# Chov2_led.net
KiCad netlist of a schematic drawn in Altium Designer
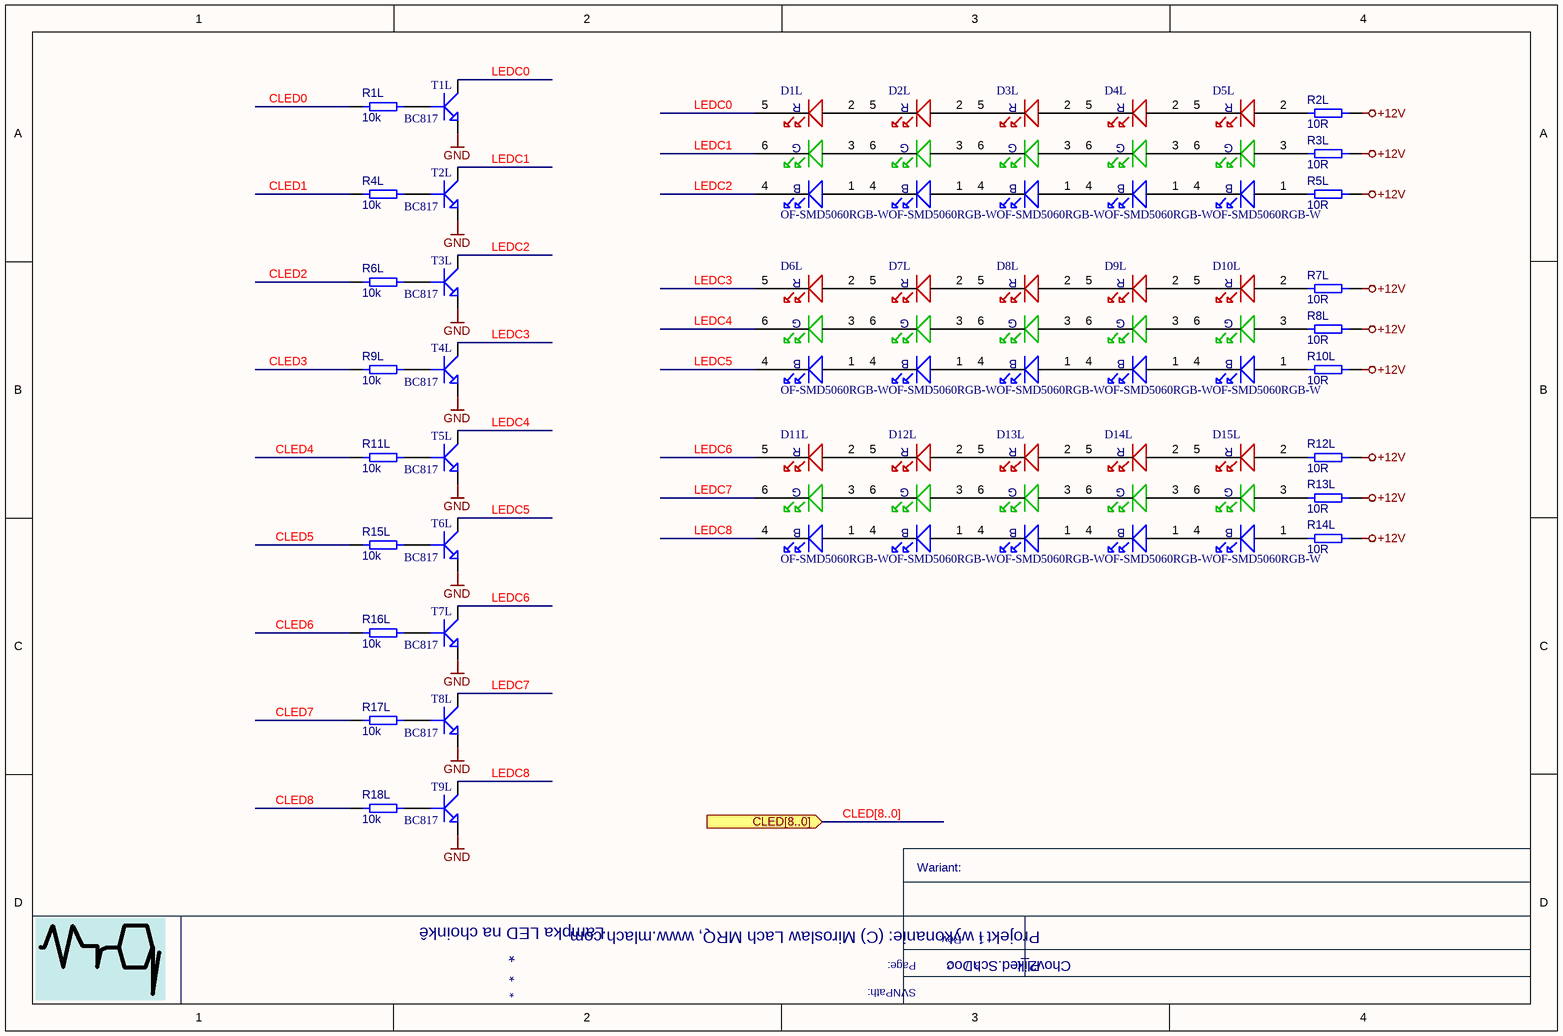
[diagram p0: Chov2_led.SchDoc]

(export (version "E")
  (design (tool "Eeschema 10.0.6"))
  (components
    (comp (ref "D1L")
      (value "OF-SMD5060RGB-W")
      (footprint "OF-SMD5060RGB-W")
      (libsource (lib "Parts") (part "OF-SMD5060RGB-W"))
    )
    (comp (ref "D2L")
      (value "OF-SMD5060RGB-W")
      (footprint "OF-SMD5060RGB-W")
      (libsource (lib "Parts") (part "OF-SMD5060RGB-W"))
    )
    (comp (ref "D3L")
      (value "OF-SMD5060RGB-W")
      (footprint "OF-SMD5060RGB-W")
      (libsource (lib "Parts") (part "OF-SMD5060RGB-W"))
    )
    (comp (ref "D4L")
      (value "OF-SMD5060RGB-W")
      (footprint "OF-SMD5060RGB-W")
      (libsource (lib "Parts") (part "OF-SMD5060RGB-W"))
    )
    (comp (ref "D5L")
      (value "OF-SMD5060RGB-W")
      (footprint "OF-SMD5060RGB-W")
      (libsource (lib "Parts") (part "OF-SMD5060RGB-W"))
    )
    (comp (ref "D6L")
      (value "OF-SMD5060RGB-W")
      (footprint "OF-SMD5060RGB-W")
      (libsource (lib "Parts") (part "OF-SMD5060RGB-W"))
    )
    (comp (ref "D7L")
      (value "OF-SMD5060RGB-W")
      (footprint "OF-SMD5060RGB-W")
      (libsource (lib "Parts") (part "OF-SMD5060RGB-W"))
    )
    (comp (ref "D8L")
      (value "OF-SMD5060RGB-W")
      (footprint "OF-SMD5060RGB-W")
      (libsource (lib "Parts") (part "OF-SMD5060RGB-W"))
    )
    (comp (ref "D9L")
      (value "OF-SMD5060RGB-W")
      (footprint "OF-SMD5060RGB-W")
      (libsource (lib "Parts") (part "OF-SMD5060RGB-W"))
    )
    (comp (ref "D10L")
      (value "OF-SMD5060RGB-W")
      (footprint "OF-SMD5060RGB-W")
      (libsource (lib "Parts") (part "OF-SMD5060RGB-W"))
    )
    (comp (ref "D11L")
      (value "OF-SMD5060RGB-W")
      (footprint "OF-SMD5060RGB-W")
      (libsource (lib "Parts") (part "OF-SMD5060RGB-W"))
    )
    (comp (ref "D12L")
      (value "OF-SMD5060RGB-W")
      (footprint "OF-SMD5060RGB-W")
      (libsource (lib "Parts") (part "OF-SMD5060RGB-W"))
    )
    (comp (ref "D13L")
      (value "OF-SMD5060RGB-W")
      (footprint "OF-SMD5060RGB-W")
      (libsource (lib "Parts") (part "OF-SMD5060RGB-W"))
    )
    (comp (ref "D14L")
      (value "OF-SMD5060RGB-W")
      (footprint "OF-SMD5060RGB-W")
      (libsource (lib "Parts") (part "OF-SMD5060RGB-W"))
    )
    (comp (ref "D15L")
      (value "OF-SMD5060RGB-W")
      (footprint "OF-SMD5060RGB-W")
      (libsource (lib "Parts") (part "OF-SMD5060RGB-W"))
    )
    (comp (ref "R1L")
      (value "0603WGF10KT5E")
      (footprint "0603-IPC")
      (fields (field (name "OTHERPARAMS") "10k") (field (name "TOLERANCE") "1%"))
      (libsource (lib "Parts") (part "R"))
    )
    (comp (ref "R2L")
      (value "0805S8F100JT5E")
      (footprint "0805")
      (fields (field (name "OTHERPARAMS") "10R") (field (name "TOLERANCE") "1%"))
      (libsource (lib "Parts") (part "R"))
    )
    (comp (ref "R3L")
      (value "0805S8F100JT5E")
      (footprint "0805")
      (fields (field (name "OTHERPARAMS") "10R") (field (name "TOLERANCE") "1%"))
      (libsource (lib "Parts") (part "R"))
    )
    (comp (ref "R4L")
      (value "0603WGF10KT5E")
      (footprint "0603-IPC")
      (fields (field (name "OTHERPARAMS") "10k") (field (name "TOLERANCE") "1%"))
      (libsource (lib "Parts") (part "R"))
    )
    (comp (ref "R5L")
      (value "0805S8F100JT5E")
      (footprint "0805")
      (fields (field (name "OTHERPARAMS") "10R") (field (name "TOLERANCE") "1%"))
      (libsource (lib "Parts") (part "R"))
    )
    (comp (ref "R6L")
      (value "0603WGF10KT5E")
      (footprint "0603-IPC")
      (fields (field (name "OTHERPARAMS") "10k") (field (name "TOLERANCE") "1%"))
      (libsource (lib "Parts") (part "R"))
    )
    (comp (ref "R7L")
      (value "0805S8F100JT5E")
      (footprint "0805")
      (fields (field (name "OTHERPARAMS") "10R") (field (name "TOLERANCE") "1%"))
      (libsource (lib "Parts") (part "R"))
    )
    (comp (ref "R8L")
      (value "0805S8F100JT5E")
      (footprint "0805")
      (fields (field (name "OTHERPARAMS") "10R") (field (name "TOLERANCE") "1%"))
      (libsource (lib "Parts") (part "R"))
    )
    (comp (ref "R9L")
      (value "0603WGF10KT5E")
      (footprint "0603-IPC")
      (fields (field (name "OTHERPARAMS") "10k") (field (name "TOLERANCE") "1%"))
      (libsource (lib "Parts") (part "R"))
    )
    (comp (ref "R10L")
      (value "0805S8F100JT5E")
      (footprint "0805")
      (fields (field (name "OTHERPARAMS") "10R") (field (name "TOLERANCE") "1%"))
      (libsource (lib "Parts") (part "R"))
    )
    (comp (ref "R11L")
      (value "0603WGF10KT5E")
      (footprint "0603-IPC")
      (fields (field (name "OTHERPARAMS") "10k") (field (name "TOLERANCE") "1%"))
      (libsource (lib "Parts") (part "R"))
    )
    (comp (ref "R12L")
      (value "0805S8F100JT5E")
      (footprint "0805")
      (fields (field (name "OTHERPARAMS") "10R") (field (name "TOLERANCE") "1%"))
      (libsource (lib "Parts") (part "R"))
    )
    (comp (ref "R13L")
      (value "0805S8F100JT5E")
      (footprint "0805")
      (fields (field (name "OTHERPARAMS") "10R") (field (name "TOLERANCE") "1%"))
      (libsource (lib "Parts") (part "R"))
    )
    (comp (ref "R14L")
      (value "0805S8F100JT5E")
      (footprint "0805")
      (fields (field (name "OTHERPARAMS") "10R") (field (name "TOLERANCE") "1%"))
      (libsource (lib "Parts") (part "R"))
    )
    (comp (ref "R15L")
      (value "0603WGF10KT5E")
      (footprint "0603-IPC")
      (fields (field (name "OTHERPARAMS") "10k") (field (name "TOLERANCE") "1%"))
      (libsource (lib "Parts") (part "R"))
    )
    (comp (ref "R16L")
      (value "0603WGF10KT5E")
      (footprint "0603-IPC")
      (fields (field (name "OTHERPARAMS") "10k") (field (name "TOLERANCE") "1%"))
      (libsource (lib "Parts") (part "R"))
    )
    (comp (ref "R17L")
      (value "0603WGF10KT5E")
      (footprint "0603-IPC")
      (fields (field (name "OTHERPARAMS") "10k") (field (name "TOLERANCE") "1%"))
      (libsource (lib "Parts") (part "R"))
    )
    (comp (ref "R18L")
      (value "0603WGF10KT5E")
      (footprint "0603-IPC")
      (fields (field (name "OTHERPARAMS") "10k") (field (name "TOLERANCE") "1%"))
      (libsource (lib "Parts") (part "R"))
    )
    (comp (ref "T1L") (value "BC817") (footprint "SOT23-3") (libsource (lib "Parts") (part "NPN_SOT23-3")))
    (comp (ref "T2L") (value "BC817") (footprint "SOT23-3") (libsource (lib "Parts") (part "NPN_SOT23-3")))
    (comp (ref "T3L") (value "BC817") (footprint "SOT23-3") (libsource (lib "Parts") (part "NPN_SOT23-3")))
    (comp (ref "T4L") (value "BC817") (footprint "SOT23-3") (libsource (lib "Parts") (part "NPN_SOT23-3")))
    (comp (ref "T5L") (value "BC817") (footprint "SOT23-3") (libsource (lib "Parts") (part "NPN_SOT23-3")))
    (comp (ref "T6L") (value "BC817") (footprint "SOT23-3") (libsource (lib "Parts") (part "NPN_SOT23-3")))
    (comp (ref "T7L") (value "BC817") (footprint "SOT23-3") (libsource (lib "Parts") (part "NPN_SOT23-3")))
    (comp (ref "T8L") (value "BC817") (footprint "SOT23-3") (libsource (lib "Parts") (part "NPN_SOT23-3")))
    (comp (ref "T9L") (value "BC817") (footprint "SOT23-3") (libsource (lib "Parts") (part "NPN_SOT23-3")))
  )
  (nets
    (net (code "1") (name "+12V") (class "Default")
      (node (ref "R10L") (pin "2") (pinfunction "2_2") (pintype "passive"))
      (node (ref "R12L") (pin "2") (pinfunction "2_2") (pintype "passive"))
      (node (ref "R13L") (pin "2") (pinfunction "2_2") (pintype "passive"))
      (node (ref "R14L") (pin "2") (pinfunction "2_2") (pintype "passive"))
      (node (ref "R2L") (pin "2") (pinfunction "2_2") (pintype "passive"))
      (node (ref "R3L") (pin "2") (pinfunction "2_2") (pintype "passive"))
      (node (ref "R5L") (pin "2") (pinfunction "2_2") (pintype "passive"))
      (node (ref "R7L") (pin "2") (pinfunction "2_2") (pintype "passive"))
      (node (ref "R8L") (pin "2") (pinfunction "2_2") (pintype "passive"))
    )
    (net (code "2") (name "/CLED0") (class "Default")
      (node (ref "R1L") (pin "1") (pinfunction "1_1") (pintype "passive"))
    )
    (net (code "3") (name "/CLED1") (class "Default")
      (node (ref "R4L") (pin "1") (pinfunction "1_1") (pintype "passive"))
    )
    (net (code "4") (name "/CLED2") (class "Default")
      (node (ref "R6L") (pin "1") (pinfunction "1_1") (pintype "passive"))
    )
    (net (code "5") (name "/CLED3") (class "Default")
      (node (ref "R9L") (pin "1") (pinfunction "1_1") (pintype "passive"))
    )
    (net (code "6") (name "/CLED4") (class "Default")
      (node (ref "R11L") (pin "1") (pinfunction "1_1") (pintype "passive"))
    )
    (net (code "7") (name "/CLED5") (class "Default")
      (node (ref "R15L") (pin "1") (pinfunction "1_1") (pintype "passive"))
    )
    (net (code "8") (name "/CLED6") (class "Default")
      (node (ref "R16L") (pin "1") (pinfunction "1_1") (pintype "passive"))
    )
    (net (code "9") (name "/CLED7") (class "Default")
      (node (ref "R17L") (pin "1") (pinfunction "1_1") (pintype "passive"))
    )
    (net (code "10") (name "/CLED8") (class "Default")
      (node (ref "R18L") (pin "1") (pinfunction "1_1") (pintype "passive"))
    )
    (net (code "12") (name "/LEDC0") (class "Default")
      (node (ref "D1L") (pin "5") (pinfunction "CATH_5") (pintype "passive"))
      (node (ref "T1L") (pin "3") (pinfunction "3_3") (pintype "passive"))
    )
    (net (code "13") (name "/LEDC1") (class "Default")
      (node (ref "D1L") (pin "6") (pinfunction "CATH_6") (pintype "passive"))
      (node (ref "T2L") (pin "3") (pinfunction "3_3") (pintype "passive"))
    )
    (net (code "14") (name "/LEDC2") (class "Default")
      (node (ref "D1L") (pin "4") (pinfunction "CATH_4") (pintype "passive"))
      (node (ref "T3L") (pin "3") (pinfunction "3_3") (pintype "passive"))
    )
    (net (code "15") (name "/LEDC3") (class "Default")
      (node (ref "D6L") (pin "5") (pinfunction "CATH_5") (pintype "passive"))
      (node (ref "T4L") (pin "3") (pinfunction "3_3") (pintype "passive"))
    )
    (net (code "16") (name "/LEDC4") (class "Default")
      (node (ref "D6L") (pin "6") (pinfunction "CATH_6") (pintype "passive"))
      (node (ref "T5L") (pin "3") (pinfunction "3_3") (pintype "passive"))
    )
    (net (code "17") (name "/LEDC5") (class "Default")
      (node (ref "D6L") (pin "4") (pinfunction "CATH_4") (pintype "passive"))
      (node (ref "T6L") (pin "3") (pinfunction "3_3") (pintype "passive"))
    )
    (net (code "18") (name "/LEDC6") (class "Default")
      (node (ref "D11L") (pin "5") (pinfunction "CATH_5") (pintype "passive"))
      (node (ref "T7L") (pin "3") (pinfunction "3_3") (pintype "passive"))
    )
    (net (code "19") (name "/LEDC7") (class "Default")
      (node (ref "D11L") (pin "6") (pinfunction "CATH_6") (pintype "passive"))
      (node (ref "T8L") (pin "3") (pinfunction "3_3") (pintype "passive"))
    )
    (net (code "20") (name "/LEDC8") (class "Default")
      (node (ref "D11L") (pin "4") (pinfunction "CATH_4") (pintype "passive"))
      (node (ref "T9L") (pin "3") (pinfunction "3_3") (pintype "passive"))
    )
    (net (code "21") (name "GND") (class "Default")
      (node (ref "T1L") (pin "2") (pinfunction "2_2") (pintype "passive"))
      (node (ref "T2L") (pin "2") (pinfunction "2_2") (pintype "passive"))
      (node (ref "T3L") (pin "2") (pinfunction "2_2") (pintype "passive"))
      (node (ref "T4L") (pin "2") (pinfunction "2_2") (pintype "passive"))
      (node (ref "T5L") (pin "2") (pinfunction "2_2") (pintype "passive"))
      (node (ref "T6L") (pin "2") (pinfunction "2_2") (pintype "passive"))
      (node (ref "T7L") (pin "2") (pinfunction "2_2") (pintype "passive"))
      (node (ref "T8L") (pin "2") (pinfunction "2_2") (pintype "passive"))
      (node (ref "T9L") (pin "2") (pinfunction "2_2") (pintype "passive"))
    )
    (net (code "22") (name "Net-(D1L-ANOD-Pad1)") (class "Default")
      (node (ref "D1L") (pin "1") (pinfunction "ANOD_1") (pintype "passive"))
      (node (ref "D2L") (pin "4") (pinfunction "CATH_4") (pintype "passive"))
    )
    (net (code "23") (name "Net-(D1L-ANOD-Pad2)") (class "Default")
      (node (ref "D1L") (pin "2") (pinfunction "ANOD_2") (pintype "passive"))
      (node (ref "D2L") (pin "5") (pinfunction "CATH_5") (pintype "passive"))
    )
    (net (code "24") (name "Net-(D1L-ANOD-Pad3)") (class "Default")
      (node (ref "D1L") (pin "3") (pinfunction "ANOD_3") (pintype "passive"))
      (node (ref "D2L") (pin "6") (pinfunction "CATH_6") (pintype "passive"))
    )
    (net (code "25") (name "Net-(D2L-ANOD-Pad1)") (class "Default")
      (node (ref "D2L") (pin "1") (pinfunction "ANOD_1") (pintype "passive"))
      (node (ref "D3L") (pin "4") (pinfunction "CATH_4") (pintype "passive"))
    )
    (net (code "26") (name "Net-(D2L-ANOD-Pad2)") (class "Default")
      (node (ref "D2L") (pin "2") (pinfunction "ANOD_2") (pintype "passive"))
      (node (ref "D3L") (pin "5") (pinfunction "CATH_5") (pintype "passive"))
    )
    (net (code "27") (name "Net-(D2L-ANOD-Pad3)") (class "Default")
      (node (ref "D2L") (pin "3") (pinfunction "ANOD_3") (pintype "passive"))
      (node (ref "D3L") (pin "6") (pinfunction "CATH_6") (pintype "passive"))
    )
    (net (code "28") (name "Net-(D3L-ANOD-Pad1)") (class "Default")
      (node (ref "D3L") (pin "1") (pinfunction "ANOD_1") (pintype "passive"))
      (node (ref "D4L") (pin "4") (pinfunction "CATH_4") (pintype "passive"))
    )
    (net (code "29") (name "Net-(D3L-ANOD-Pad2)") (class "Default")
      (node (ref "D3L") (pin "2") (pinfunction "ANOD_2") (pintype "passive"))
      (node (ref "D4L") (pin "5") (pinfunction "CATH_5") (pintype "passive"))
    )
    (net (code "30") (name "Net-(D3L-ANOD-Pad3)") (class "Default")
      (node (ref "D3L") (pin "3") (pinfunction "ANOD_3") (pintype "passive"))
      (node (ref "D4L") (pin "6") (pinfunction "CATH_6") (pintype "passive"))
    )
    (net (code "31") (name "Net-(D4L-ANOD-Pad1)") (class "Default")
      (node (ref "D4L") (pin "1") (pinfunction "ANOD_1") (pintype "passive"))
      (node (ref "D5L") (pin "4") (pinfunction "CATH_4") (pintype "passive"))
    )
    (net (code "32") (name "Net-(D4L-ANOD-Pad2)") (class "Default")
      (node (ref "D4L") (pin "2") (pinfunction "ANOD_2") (pintype "passive"))
      (node (ref "D5L") (pin "5") (pinfunction "CATH_5") (pintype "passive"))
    )
    (net (code "33") (name "Net-(D4L-ANOD-Pad3)") (class "Default")
      (node (ref "D4L") (pin "3") (pinfunction "ANOD_3") (pintype "passive"))
      (node (ref "D5L") (pin "6") (pinfunction "CATH_6") (pintype "passive"))
    )
    (net (code "34") (name "Net-(D5L-ANOD-Pad1)") (class "Default")
      (node (ref "D5L") (pin "1") (pinfunction "ANOD_1") (pintype "passive"))
      (node (ref "R5L") (pin "1") (pinfunction "1_1") (pintype "passive"))
    )
    (net (code "35") (name "Net-(D5L-ANOD-Pad2)") (class "Default")
      (node (ref "D5L") (pin "2") (pinfunction "ANOD_2") (pintype "passive"))
      (node (ref "R2L") (pin "1") (pinfunction "1_1") (pintype "passive"))
    )
    (net (code "36") (name "Net-(D5L-ANOD-Pad3)") (class "Default")
      (node (ref "D5L") (pin "3") (pinfunction "ANOD_3") (pintype "passive"))
      (node (ref "R3L") (pin "1") (pinfunction "1_1") (pintype "passive"))
    )
    (net (code "37") (name "Net-(D6L-ANOD-Pad1)") (class "Default")
      (node (ref "D6L") (pin "1") (pinfunction "ANOD_1") (pintype "passive"))
      (node (ref "D7L") (pin "4") (pinfunction "CATH_4") (pintype "passive"))
    )
    (net (code "38") (name "Net-(D6L-ANOD-Pad2)") (class "Default")
      (node (ref "D6L") (pin "2") (pinfunction "ANOD_2") (pintype "passive"))
      (node (ref "D7L") (pin "5") (pinfunction "CATH_5") (pintype "passive"))
    )
    (net (code "39") (name "Net-(D6L-ANOD-Pad3)") (class "Default")
      (node (ref "D6L") (pin "3") (pinfunction "ANOD_3") (pintype "passive"))
      (node (ref "D7L") (pin "6") (pinfunction "CATH_6") (pintype "passive"))
    )
    (net (code "40") (name "Net-(D7L-ANOD-Pad1)") (class "Default")
      (node (ref "D7L") (pin "1") (pinfunction "ANOD_1") (pintype "passive"))
      (node (ref "D8L") (pin "4") (pinfunction "CATH_4") (pintype "passive"))
    )
    (net (code "41") (name "Net-(D7L-ANOD-Pad2)") (class "Default")
      (node (ref "D7L") (pin "2") (pinfunction "ANOD_2") (pintype "passive"))
      (node (ref "D8L") (pin "5") (pinfunction "CATH_5") (pintype "passive"))
    )
    (net (code "42") (name "Net-(D7L-ANOD-Pad3)") (class "Default")
      (node (ref "D7L") (pin "3") (pinfunction "ANOD_3") (pintype "passive"))
      (node (ref "D8L") (pin "6") (pinfunction "CATH_6") (pintype "passive"))
    )
    (net (code "43") (name "Net-(D8L-ANOD-Pad1)") (class "Default")
      (node (ref "D8L") (pin "1") (pinfunction "ANOD_1") (pintype "passive"))
      (node (ref "D9L") (pin "4") (pinfunction "CATH_4") (pintype "passive"))
    )
    (net (code "44") (name "Net-(D8L-ANOD-Pad2)") (class "Default")
      (node (ref "D8L") (pin "2") (pinfunction "ANOD_2") (pintype "passive"))
      (node (ref "D9L") (pin "5") (pinfunction "CATH_5") (pintype "passive"))
    )
    (net (code "45") (name "Net-(D8L-ANOD-Pad3)") (class "Default")
      (node (ref "D8L") (pin "3") (pinfunction "ANOD_3") (pintype "passive"))
      (node (ref "D9L") (pin "6") (pinfunction "CATH_6") (pintype "passive"))
    )
    (net (code "46") (name "Net-(D10L-ANOD-Pad1)") (class "Default")
      (node (ref "D10L") (pin "1") (pinfunction "ANOD_1") (pintype "passive"))
      (node (ref "R10L") (pin "1") (pinfunction "1_1") (pintype "passive"))
    )
    (net (code "47") (name "Net-(D10L-ANOD-Pad2)") (class "Default")
      (node (ref "D10L") (pin "2") (pinfunction "ANOD_2") (pintype "passive"))
      (node (ref "R7L") (pin "1") (pinfunction "1_1") (pintype "passive"))
    )
    (net (code "48") (name "Net-(D10L-ANOD-Pad3)") (class "Default")
      (node (ref "D10L") (pin "3") (pinfunction "ANOD_3") (pintype "passive"))
      (node (ref "R8L") (pin "1") (pinfunction "1_1") (pintype "passive"))
    )
    (net (code "49") (name "Net-(D10L-CATH-Pad4)") (class "Default")
      (node (ref "D10L") (pin "4") (pinfunction "CATH_4") (pintype "passive"))
      (node (ref "D9L") (pin "1") (pinfunction "ANOD_1") (pintype "passive"))
    )
    (net (code "50") (name "Net-(D10L-CATH-Pad5)") (class "Default")
      (node (ref "D10L") (pin "5") (pinfunction "CATH_5") (pintype "passive"))
      (node (ref "D9L") (pin "2") (pinfunction "ANOD_2") (pintype "passive"))
    )
    (net (code "51") (name "Net-(D10L-CATH-Pad6)") (class "Default")
      (node (ref "D10L") (pin "6") (pinfunction "CATH_6") (pintype "passive"))
      (node (ref "D9L") (pin "3") (pinfunction "ANOD_3") (pintype "passive"))
    )
    (net (code "52") (name "Net-(D11L-ANOD-Pad1)") (class "Default")
      (node (ref "D11L") (pin "1") (pinfunction "ANOD_1") (pintype "passive"))
      (node (ref "D12L") (pin "4") (pinfunction "CATH_4") (pintype "passive"))
    )
    (net (code "53") (name "Net-(D11L-ANOD-Pad2)") (class "Default")
      (node (ref "D11L") (pin "2") (pinfunction "ANOD_2") (pintype "passive"))
      (node (ref "D12L") (pin "5") (pinfunction "CATH_5") (pintype "passive"))
    )
    (net (code "54") (name "Net-(D11L-ANOD-Pad3)") (class "Default")
      (node (ref "D11L") (pin "3") (pinfunction "ANOD_3") (pintype "passive"))
      (node (ref "D12L") (pin "6") (pinfunction "CATH_6") (pintype "passive"))
    )
    (net (code "55") (name "Net-(D12L-ANOD-Pad1)") (class "Default")
      (node (ref "D12L") (pin "1") (pinfunction "ANOD_1") (pintype "passive"))
      (node (ref "D13L") (pin "4") (pinfunction "CATH_4") (pintype "passive"))
    )
    (net (code "56") (name "Net-(D12L-ANOD-Pad2)") (class "Default")
      (node (ref "D12L") (pin "2") (pinfunction "ANOD_2") (pintype "passive"))
      (node (ref "D13L") (pin "5") (pinfunction "CATH_5") (pintype "passive"))
    )
    (net (code "57") (name "Net-(D12L-ANOD-Pad3)") (class "Default")
      (node (ref "D12L") (pin "3") (pinfunction "ANOD_3") (pintype "passive"))
      (node (ref "D13L") (pin "6") (pinfunction "CATH_6") (pintype "passive"))
    )
    (net (code "58") (name "Net-(D13L-ANOD-Pad1)") (class "Default")
      (node (ref "D13L") (pin "1") (pinfunction "ANOD_1") (pintype "passive"))
      (node (ref "D14L") (pin "4") (pinfunction "CATH_4") (pintype "passive"))
    )
    (net (code "59") (name "Net-(D13L-ANOD-Pad2)") (class "Default")
      (node (ref "D13L") (pin "2") (pinfunction "ANOD_2") (pintype "passive"))
      (node (ref "D14L") (pin "5") (pinfunction "CATH_5") (pintype "passive"))
    )
    (net (code "60") (name "Net-(D13L-ANOD-Pad3)") (class "Default")
      (node (ref "D13L") (pin "3") (pinfunction "ANOD_3") (pintype "passive"))
      (node (ref "D14L") (pin "6") (pinfunction "CATH_6") (pintype "passive"))
    )
    (net (code "61") (name "Net-(D14L-ANOD-Pad1)") (class "Default")
      (node (ref "D14L") (pin "1") (pinfunction "ANOD_1") (pintype "passive"))
      (node (ref "D15L") (pin "4") (pinfunction "CATH_4") (pintype "passive"))
    )
    (net (code "62") (name "Net-(D14L-ANOD-Pad2)") (class "Default")
      (node (ref "D14L") (pin "2") (pinfunction "ANOD_2") (pintype "passive"))
      (node (ref "D15L") (pin "5") (pinfunction "CATH_5") (pintype "passive"))
    )
    (net (code "63") (name "Net-(D14L-ANOD-Pad3)") (class "Default")
      (node (ref "D14L") (pin "3") (pinfunction "ANOD_3") (pintype "passive"))
      (node (ref "D15L") (pin "6") (pinfunction "CATH_6") (pintype "passive"))
    )
    (net (code "64") (name "Net-(D15L-ANOD-Pad1)") (class "Default")
      (node (ref "D15L") (pin "1") (pinfunction "ANOD_1") (pintype "passive"))
      (node (ref "R14L") (pin "1") (pinfunction "1_1") (pintype "passive"))
    )
    (net (code "65") (name "Net-(D15L-ANOD-Pad2)") (class "Default")
      (node (ref "D15L") (pin "2") (pinfunction "ANOD_2") (pintype "passive"))
      (node (ref "R12L") (pin "1") (pinfunction "1_1") (pintype "passive"))
    )
    (net (code "66") (name "Net-(D15L-ANOD-Pad3)") (class "Default")
      (node (ref "D15L") (pin "3") (pinfunction "ANOD_3") (pintype "passive"))
      (node (ref "R13L") (pin "1") (pinfunction "1_1") (pintype "passive"))
    )
    (net (code "67") (name "Net-(R1L-Pad2)") (class "Default")
      (node (ref "R1L") (pin "2") (pinfunction "2_2") (pintype "passive"))
      (node (ref "T1L") (pin "1") (pinfunction "1_1") (pintype "passive"))
    )
    (net (code "68") (name "Net-(R4L-Pad2)") (class "Default")
      (node (ref "R4L") (pin "2") (pinfunction "2_2") (pintype "passive"))
      (node (ref "T2L") (pin "1") (pinfunction "1_1") (pintype "passive"))
    )
    (net (code "69") (name "Net-(R6L-Pad2)") (class "Default")
      (node (ref "R6L") (pin "2") (pinfunction "2_2") (pintype "passive"))
      (node (ref "T3L") (pin "1") (pinfunction "1_1") (pintype "passive"))
    )
    (net (code "70") (name "Net-(R9L-Pad2)") (class "Default")
      (node (ref "R9L") (pin "2") (pinfunction "2_2") (pintype "passive"))
      (node (ref "T4L") (pin "1") (pinfunction "1_1") (pintype "passive"))
    )
    (net (code "71") (name "Net-(R11L-Pad2)") (class "Default")
      (node (ref "R11L") (pin "2") (pinfunction "2_2") (pintype "passive"))
      (node (ref "T5L") (pin "1") (pinfunction "1_1") (pintype "passive"))
    )
    (net (code "72") (name "Net-(R15L-Pad2)") (class "Default")
      (node (ref "R15L") (pin "2") (pinfunction "2_2") (pintype "passive"))
      (node (ref "T6L") (pin "1") (pinfunction "1_1") (pintype "passive"))
    )
    (net (code "73") (name "Net-(R16L-Pad2)") (class "Default")
      (node (ref "R16L") (pin "2") (pinfunction "2_2") (pintype "passive"))
      (node (ref "T7L") (pin "1") (pinfunction "1_1") (pintype "passive"))
    )
    (net (code "74") (name "Net-(R17L-Pad2)") (class "Default")
      (node (ref "R17L") (pin "2") (pinfunction "2_2") (pintype "passive"))
      (node (ref "T8L") (pin "1") (pinfunction "1_1") (pintype "passive"))
    )
    (net (code "75") (name "Net-(R18L-Pad2)") (class "Default")
      (node (ref "R18L") (pin "2") (pinfunction "2_2") (pintype "passive"))
      (node (ref "T9L") (pin "1") (pinfunction "1_1") (pintype "passive"))
    )
  )
)
